# SUP_3_3_FMC.net
KiCad netlist of a schematic drawn in Altium Designer
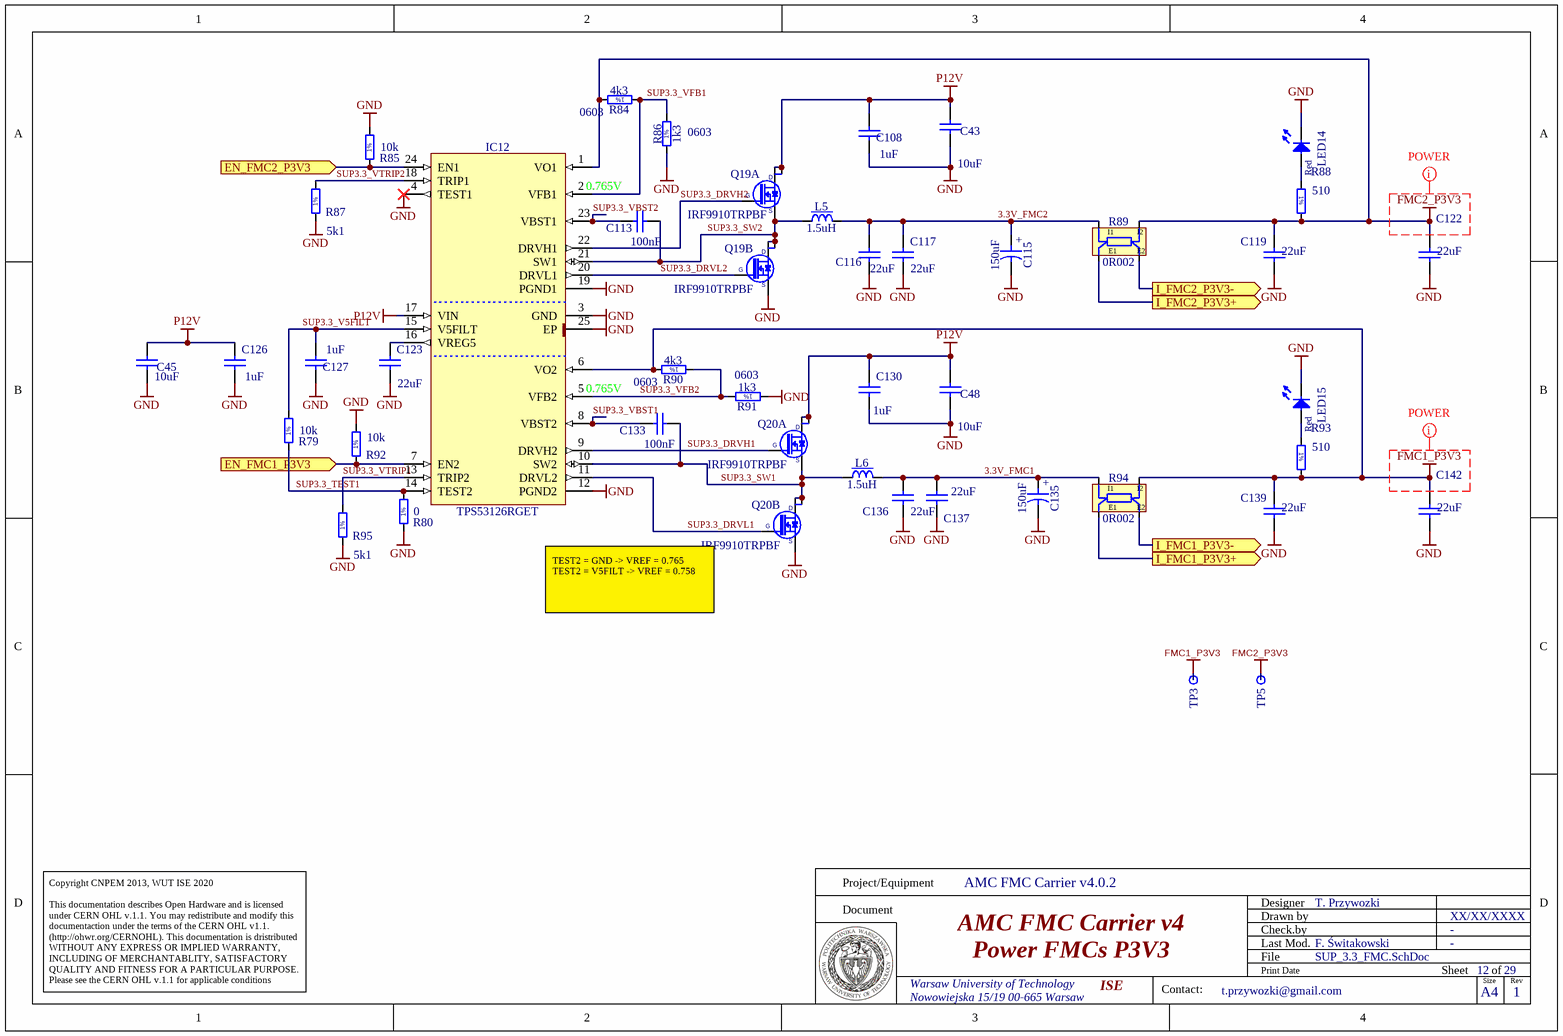
[diagram p0: SUP_3.3_FMC.SchDoc]

(export (version "E")
  (design (tool "Eeschema 10.0.6"))
  (components
    (comp (ref "C43")
      (value "10uF")
      (footprint "CAPC2012X135N")
      (description "Non-polarised capacitor")
      (fields
        (field (name "PART NUMBER") "CC0805_10UF_16V_10%_X5R")
        (field (name "VOLTAGE") "16V")
        (field (name "AUTHOR") "CERN DEM JLC")
      )
      (libsource (lib "Capacitors") (part "Capacitor - non polarized"))
    )
    (comp (ref "C45")
      (value "10uF")
      (footprint "CAPC2012X135N")
      (description "Non-polarised capacitor")
      (fields
        (field (name "PART NUMBER") "CC0805_10UF_16V_10%_X5R")
        (field (name "VOLTAGE") "16V")
        (field (name "AUTHOR") "CERN DEM JLC")
      )
      (libsource (lib "Capacitors") (part "Capacitor - non polarized"))
    )
    (comp (ref "C48")
      (value "10uF")
      (footprint "CAPC2012X135N")
      (description "Non-polarised capacitor")
      (fields
        (field (name "PART NUMBER") "CC0805_10UF_16V_10%_X5R")
        (field (name "VOLTAGE") "16V")
        (field (name "AUTHOR") "CERN DEM JLC")
      )
      (libsource (lib "Capacitors") (part "Capacitor - non polarized"))
    )
    (comp (ref "C108")
      (value "1uF")
      (footprint "CAPC1608X87N")
      (description "Non-polarised capacitor")
      (fields
        (field (name "PART NUMBER") "CC0603_1UF_16V_10%_X7R")
        (field (name "VOLTAGE") "16V")
        (field (name "AUTHOR") "CERN DEM JLC")
      )
      (libsource (lib "Capacitors") (part "Capacitor - non polarized"))
    )
    (comp (ref "C113")
      (value "100nF")
      (footprint "CAPC1005X55N")
      (description "Non-polarised capacitor")
      (fields
        (field (name "PART NUMBER") "CC0402_100NF_16V_10%_X7R")
        (field (name "VOLTAGE") "16V")
        (field (name "AUTHOR") "CERN DEM JLC")
      )
      (libsource (lib "Capacitors") (part "Capacitor - non polarized"))
    )
    (comp (ref "C115")
      (value "150uF")
      (footprint "CAPMP7343X200N")
      (description "Polarised capacitor")
      (fields
        (field (name "PART NUMBER") "CAEM7343-20_150UF_4V_20%_LESR0016")
        (field (name "VOLTAGE") "4V")
        (field (name "AUTHOR") "CERN DEM JLC")
      )
      (libsource (lib "Capacitors") (part "Capacitor - polarized"))
    )
    (comp (ref "C116")
      (value "22uF")
      (footprint "CAPC3216X180N")
      (description "Non-polarised capacitor")
      (fields
        (field (name "PART NUMBER") "CC1206_22UF_10V_10%_X7R")
        (field (name "VOLTAGE") "10V")
        (field (name "AUTHOR") "CERN DEM JLC")
      )
      (libsource (lib "Capacitors") (part "Capacitor - non polarized"))
    )
    (comp (ref "C117")
      (value "22uF")
      (footprint "CAPC3216X180N")
      (description "Non-polarised capacitor")
      (fields
        (field (name "PART NUMBER") "CC1206_22UF_10V_10%_X7R")
        (field (name "VOLTAGE") "10V")
        (field (name "AUTHOR") "CERN DEM JLC")
      )
      (libsource (lib "Capacitors") (part "Capacitor - non polarized"))
    )
    (comp (ref "C119")
      (value "22uF")
      (footprint "CAPC3216X180N")
      (description "Non-polarised capacitor")
      (fields
        (field (name "PART NUMBER") "CC1206_22UF_10V_10%_X7R")
        (field (name "VOLTAGE") "10V")
        (field (name "AUTHOR") "CERN DEM JLC")
      )
      (libsource (lib "Capacitors") (part "Capacitor - non polarized"))
    )
    (comp (ref "C122")
      (value "22uF")
      (footprint "CAPC3216X180N")
      (description "Non-polarised capacitor")
      (fields
        (field (name "PART NUMBER") "CC1206_22UF_10V_10%_X7R")
        (field (name "VOLTAGE") "10V")
        (field (name "AUTHOR") "CERN DEM JLC")
      )
      (libsource (lib "Capacitors") (part "Capacitor - non polarized"))
    )
    (comp (ref "C123")
      (value "22uF")
      (footprint "CAPC3216X180N")
      (description "Non-polarised capacitor")
      (fields
        (field (name "PART NUMBER") "CC1206_22UF_10V_10%_X7R")
        (field (name "VOLTAGE") "10V")
        (field (name "AUTHOR") "CERN DEM JLC")
      )
      (libsource (lib "Capacitors") (part "Capacitor - non polarized"))
    )
    (comp (ref "C126")
      (value "1uF")
      (footprint "CAPC1608X87N")
      (description "Non-polarised capacitor")
      (fields
        (field (name "PART NUMBER") "CC0603_1UF_16V_10%_X7R")
        (field (name "VOLTAGE") "16V")
        (field (name "AUTHOR") "CERN DEM JLC")
      )
      (libsource (lib "Capacitors") (part "Capacitor - non polarized"))
    )
    (comp (ref "C127")
      (value "1uF")
      (footprint "CAPC1608X87N")
      (description "Non-polarised capacitor")
      (fields
        (field (name "PART NUMBER") "CC0603_1UF_16V_10%_X7R")
        (field (name "VOLTAGE") "16V")
        (field (name "AUTHOR") "CERN DEM JLC")
      )
      (libsource (lib "Capacitors") (part "Capacitor - non polarized"))
    )
    (comp (ref "C130")
      (value "1uF")
      (footprint "CAPC1608X87N")
      (description "Non-polarised capacitor")
      (fields
        (field (name "PART NUMBER") "CC0603_1UF_16V_10%_X7R")
        (field (name "VOLTAGE") "16V")
        (field (name "AUTHOR") "CERN DEM JLC")
      )
      (libsource (lib "Capacitors") (part "Capacitor - non polarized"))
    )
    (comp (ref "C133")
      (value "100nF")
      (footprint "CAPC1005X55N")
      (description "Non-polarised capacitor")
      (fields
        (field (name "PART NUMBER") "CC0402_100NF_16V_10%_X7R")
        (field (name "VOLTAGE") "16V")
        (field (name "AUTHOR") "CERN DEM JLC")
      )
      (libsource (lib "Capacitors") (part "Capacitor - non polarized"))
    )
    (comp (ref "C135")
      (value "150uF")
      (footprint "CAPMP7343X200N")
      (description "Polarised capacitor")
      (fields
        (field (name "PART NUMBER") "CAEM7343-20_150UF_4V_20%_LESR0016")
        (field (name "VOLTAGE") "4V")
        (field (name "AUTHOR") "CERN DEM JLC")
      )
      (libsource (lib "Capacitors") (part "Capacitor - polarized"))
    )
    (comp (ref "C136")
      (value "22uF")
      (footprint "CAPC3216X180N")
      (description "Non-polarised capacitor")
      (fields
        (field (name "PART NUMBER") "CC1206_22UF_10V_10%_X7R")
        (field (name "VOLTAGE") "10V")
        (field (name "AUTHOR") "CERN DEM JLC")
      )
      (libsource (lib "Capacitors") (part "Capacitor - non polarized"))
    )
    (comp (ref "C137")
      (value "22uF")
      (footprint "CAPC3216X180N")
      (description "Non-polarised capacitor")
      (fields
        (field (name "PART NUMBER") "CC1206_22UF_10V_10%_X7R")
        (field (name "VOLTAGE") "10V")
        (field (name "AUTHOR") "CERN DEM JLC")
      )
      (libsource (lib "Capacitors") (part "Capacitor - non polarized"))
    )
    (comp (ref "C139")
      (value "22uF")
      (footprint "CAPC3216X180N")
      (description "Non-polarised capacitor")
      (fields
        (field (name "PART NUMBER") "CC1206_22UF_10V_10%_X7R")
        (field (name "VOLTAGE") "10V")
        (field (name "AUTHOR") "CERN DEM JLC")
      )
      (libsource (lib "Capacitors") (part "Capacitor - non polarized"))
    )
    (comp (ref "C142")
      (value "22uF")
      (footprint "CAPC3216X180N")
      (description "Non-polarised capacitor")
      (fields
        (field (name "PART NUMBER") "CC1206_22UF_10V_10%_X7R")
        (field (name "VOLTAGE") "10V")
        (field (name "AUTHOR") "CERN DEM JLC")
      )
      (libsource (lib "Capacitors") (part "Capacitor - non polarized"))
    )
    (comp (ref "IC12")
      (value "TPS53126RGET")
      (footprint "QFN50P400X400X100-25N-S255")
      (description "Dual Synchronous Step-Down Controller For Low Voltage Power Rails")
      (fields (field (name "MANUFACTURER") "TEXAS INSTRUMENTS") (field (name "AUTHOR") "CERN DEM JLC"))
      (libsource (lib "ICs And Semiconductors") (part "TPS53126RGET"))
    )
    (comp (ref "L5")
      (value "1.5uH")
      (footprint "IND_TDK_SPM6530")
      (description "Inductor With Core")
      (fields
        (field (name "PART NUMBER") "IND_1.5UH_20%_TDK_SPM6530")
        (field (name "POWER") "11A")
        (field (name "AUTHOR") "CERN DEM MR")
      )
      (libsource (lib "Inductors & Transformers") (part "Inductor With Magnetic core"))
    )
    (comp (ref "L6")
      (value "1.5uH")
      (footprint "IND_TDK_SPM6530")
      (description "Inductor With Core")
      (fields
        (field (name "PART NUMBER") "IND_1.5UH_20%_TDK_SPM6530")
        (field (name "POWER") "11A")
        (field (name "AUTHOR") "CERN DEM MR")
      )
      (libsource (lib "Inductors & Transformers") (part "Inductor With Magnetic core"))
    )
    (comp (ref "LED14")
      (value "Red")
      (footprint "LED_KINGBRIGHT_KPH-1608SURCK")
      (description "LED Red 1C 2A")
      (fields
        (field (name "PART NUMBER") "LED_KINGBRIGHT_KPH-1608SURCK")
        (field (name "MANUFACTURER") "KINGBRIGHT")
        (field (name "AUTHOR") "CERN DEM JLC")
      )
      (libsource (lib "ICs And Semiconductors") (part "LED Red 1C 2A"))
    )
    (comp (ref "LED15")
      (value "Red")
      (footprint "LED_KINGBRIGHT_KPH-1608SURCK")
      (description "LED Red 1C 2A")
      (fields
        (field (name "PART NUMBER") "LED_KINGBRIGHT_KPH-1608SURCK")
        (field (name "MANUFACTURER") "KINGBRIGHT")
        (field (name "AUTHOR") "CERN DEM JLC")
      )
      (libsource (lib "ICs And Semiconductors") (part "LED Red 1C 2A"))
    )
    (comp (ref "Q19")
      (value "IRF9910TRPBF")
      (footprint "SOIC127P600X175-8N")
      (description "Dual SO-8 MOSFET For POL Cconverter")
      (fields (field (name "MANUFACTURER") "INTERNATIONAL RECTIFIER") (field (name "AUTHOR") "TP"))
      (libsource (lib "AMC_FMC_Carrier") (part "IRF9910"))
    )
    (comp (ref "Q20")
      (value "IRF9910TRPBF")
      (footprint "SOIC127P600X175-8N")
      (description "Dual SO-8 MOSFET For POL Cconverter")
      (fields (field (name "MANUFACTURER") "INTERNATIONAL RECTIFIER") (field (name "AUTHOR") "TP"))
      (libsource (lib "AMC_FMC_Carrier") (part "IRF9910"))
    )
    (comp (ref "R79")
      (value "10k")
      (footprint "RESC1005X40N")
      (description "Resistor - 1%")
      (fields
        (field (name "PART NUMBER") "R0402_10K_1%_0.0625W_100PPM")
        (field (name "POWER") "0.0625W")
        (field (name "AUTHOR") "CERN DEM JLC")
      )
      (libsource (lib "Resistors") (part "Resistor - 1%"))
    )
    (comp (ref "R80")
      (value "0")
      (footprint "RESC1005X40N")
      (description "Resistor - 1%")
      (fields
        (field (name "PART NUMBER") "R0402_0R_JUMPER")
        (field (name "MANUFACTURER") "GENERIC")
        (field (name "AUTHOR") "CERN DEM JLC")
      )
      (libsource (lib "Resistors") (part "Resistor - 1%"))
    )
    (comp (ref "R84")
      (value "4k3")
      (footprint "RESC1608X55N")
      (description "Resistor - 1%")
      (fields
        (field (name "PART NUMBER") "R0603_4K3_1%_0.1W_100PPM")
        (field (name "POWER") "0.1W")
        (field (name "CASE") "0603")
        (field (name "AUTHOR") "CERN DEM JLC")
      )
      (libsource (lib "Resistors") (part "Resistor - 1%"))
    )
    (comp (ref "R85")
      (value "10k")
      (footprint "RESC1005X40N")
      (description "Resistor - 1%")
      (fields
        (field (name "PART NUMBER") "R0402_10K_1%_0.0625W_100PPM")
        (field (name "POWER") "0.0625W")
        (field (name "AUTHOR") "CERN DEM JLC")
      )
      (libsource (lib "Resistors") (part "Resistor - 1%"))
    )
    (comp (ref "R86")
      (value "1k3")
      (footprint "RESC1608X55N")
      (description "Resistor - 1%")
      (fields
        (field (name "PART NUMBER") "R0603_1K3_1%_0.1W_100PPM")
        (field (name "POWER") "0.1W")
        (field (name "CASE") "0603")
        (field (name "AUTHOR") "CERN DEM JLC")
      )
      (libsource (lib "Resistors") (part "Resistor - 1%"))
    )
    (comp (ref "R87")
      (value "5k1")
      (footprint "RESC1608X55N")
      (description "Resistor - 1%")
      (fields
        (field (name "PART NUMBER") "R0603_5K1_1%_0.1W_100PPM")
        (field (name "POWER") "0.1W")
        (field (name "AUTHOR") "CERN DEM JLC")
      )
      (libsource (lib "Resistors") (part "Resistor - 1%"))
    )
    (comp (ref "R88")
      (value "510")
      (footprint "RESC1005X40N")
      (description "Resistor - 1%")
      (fields
        (field (name "PART NUMBER") "R0402_510R_1%_0.0625W_100PPM")
        (field (name "POWER") "0.0625W")
        (field (name "AUTHOR") "CERN DEM JLC")
      )
      (libsource (lib "Resistors") (part "Resistor - 1%"))
    )
    (comp (ref "R89")
      (value "0R002")
      (footprint "RES_VISHAY_WSK2512_0R005-0R2")
      (description "Power and Current Sensing Resistor")
      (fields
        (field (name "PART NUMBER") "R2512_0R002_1%_1W_35PPM_VISHAY_WSK")
        (field (name "POWER") "1W")
        (field (name "AUTHOR") "CERN DEM MR")
      )
      (libsource (lib "Resistors") (part "Current Sense Resistor"))
    )
    (comp (ref "R90")
      (value "4k3")
      (footprint "RESC1608X55N")
      (description "Resistor - 1%")
      (fields
        (field (name "PART NUMBER") "R0603_4K3_1%_0.1W_100PPM")
        (field (name "POWER") "0.1W")
        (field (name "CASE") "0603")
        (field (name "AUTHOR") "CERN DEM JLC")
      )
      (libsource (lib "Resistors") (part "Resistor - 1%"))
    )
    (comp (ref "R91")
      (value "1k3")
      (footprint "RESC1608X55N")
      (description "Resistor - 1%")
      (fields
        (field (name "PART NUMBER") "R0603_1K3_1%_0.1W_100PPM")
        (field (name "POWER") "0.1W")
        (field (name "CASE") "0603")
        (field (name "AUTHOR") "CERN DEM JLC")
      )
      (libsource (lib "Resistors") (part "Resistor - 1%"))
    )
    (comp (ref "R92")
      (value "10k")
      (footprint "RESC1005X40N")
      (description "Resistor - 1%")
      (fields
        (field (name "PART NUMBER") "R0402_10K_1%_0.0625W_100PPM")
        (field (name "POWER") "0.0625W")
        (field (name "AUTHOR") "CERN DEM JLC")
      )
      (libsource (lib "Resistors") (part "Resistor - 1%"))
    )
    (comp (ref "R93")
      (value "510")
      (footprint "RESC1005X40N")
      (description "Resistor - 1%")
      (fields
        (field (name "PART NUMBER") "R0402_510R_1%_0.0625W_100PPM")
        (field (name "POWER") "0.0625W")
        (field (name "AUTHOR") "CERN DEM JLC")
      )
      (libsource (lib "Resistors") (part "Resistor - 1%"))
    )
    (comp (ref "R94")
      (value "0R002")
      (footprint "RES_VISHAY_WSK2512_0R005-0R2")
      (description "Power and Current Sensing Resistor")
      (fields
        (field (name "PART NUMBER") "R2512_0R002_1%_1W_35PPM_VISHAY_WSK")
        (field (name "POWER") "1W")
        (field (name "AUTHOR") "CERN DEM MR")
      )
      (libsource (lib "Resistors") (part "Current Sense Resistor"))
    )
    (comp (ref "R95")
      (value "5k1")
      (footprint "RESC1608X55N")
      (description "Resistor - 1%")
      (fields
        (field (name "PART NUMBER") "R0603_5K1_1%_0.1W_100PPM")
        (field (name "POWER") "0.1W")
        (field (name "AUTHOR") "CERN DEM JLC")
      )
      (libsource (lib "Resistors") (part "Resistor - 1%"))
    )
    (comp (ref "TP3")
      (value "Test Point")
      (footprint "TPS127")
      (fields (field (name "PART NUMBER") "SMD_PAD_1.27X1.27MM") (field (name "AUTHOR") "CERN DEM JLC"))
      (libsource (lib "Eletro-mechanical") (part "Test Point"))
    )
    (comp (ref "TP5")
      (value "Test Point")
      (footprint "TPS127")
      (fields (field (name "PART NUMBER") "SMD_PAD_1.27X1.27MM") (field (name "AUTHOR") "CERN DEM JLC"))
      (libsource (lib "Eletro-mechanical") (part "Test Point"))
    )
  )
  (nets
    (net (code "1") (name "/3.3V_FMC1") (class "Default")
      (node (ref "C135") (pin "1") (pinfunction "1_1") (pintype "passive"))
      (node (ref "C136") (pin "1") (pinfunction "1_1") (pintype "passive"))
      (node (ref "C137") (pin "1") (pinfunction "1_1") (pintype "passive"))
      (node (ref "L6") (pin "2") (pinfunction "2_2") (pintype "passive"))
      (node (ref "R94") (pin "I1") (pinfunction "I1_I1") (pintype "passive"))
    )
    (net (code "2") (name "/3.3V_FMC2") (class "Default")
      (node (ref "C115") (pin "1") (pinfunction "1_1") (pintype "passive"))
      (node (ref "C116") (pin "1") (pinfunction "1_1") (pintype "passive"))
      (node (ref "C117") (pin "1") (pinfunction "1_1") (pintype "passive"))
      (node (ref "L5") (pin "2") (pinfunction "2_2") (pintype "passive"))
      (node (ref "R89") (pin "I1") (pinfunction "I1_I1") (pintype "passive"))
    )
    (net (code "3") (name "/EN_FMC1_P3V3") (class "Default")
      (node (ref "IC12") (pin "7") (pinfunction "EN2_7") (pintype "input"))
      (node (ref "R92") (pin "1") (pinfunction "1_1") (pintype "passive"))
    )
    (net (code "4") (name "/EN_FMC2_P3V3") (class "Default")
      (node (ref "IC12") (pin "24") (pinfunction "EN1_24") (pintype "input"))
      (node (ref "R85") (pin "1") (pinfunction "1_1") (pintype "passive"))
    )
    (net (code "5") (name "/I_FMC1_P3V3+") (class "Default")
      (node (ref "R94") (pin "E1") (pinfunction "E1_E1") (pintype "passive"))
    )
    (net (code "6") (name "/I_FMC1_P3V3-") (class "Default")
      (node (ref "R94") (pin "E2") (pinfunction "E2_E2") (pintype "passive"))
    )
    (net (code "7") (name "/I_FMC2_P3V3+") (class "Default")
      (node (ref "R89") (pin "E1") (pinfunction "E1_E1") (pintype "passive"))
    )
    (net (code "8") (name "/I_FMC2_P3V3-") (class "Default")
      (node (ref "R89") (pin "E2") (pinfunction "E2_E2") (pintype "passive"))
    )
    (net (code "9") (name "/SUP3.3_DRVH1") (class "Default")
      (node (ref "IC12") (pin "9") (pinfunction "DRVH2_9") (pintype "output"))
      (node (ref "Q20") (pin "4") (pinfunction "G_4") (pintype "passive"))
    )
    (net (code "10") (name "/SUP3.3_DRVH2") (class "Default")
      (node (ref "IC12") (pin "22") (pinfunction "DRVH1_22") (pintype "output"))
      (node (ref "Q19") (pin "4") (pinfunction "G_4") (pintype "passive"))
    )
    (net (code "11") (name "/SUP3.3_DRVL1") (class "Default")
      (node (ref "IC12") (pin "11") (pinfunction "DRVL2_11") (pintype "output"))
      (node (ref "Q20") (pin "2") (pinfunction "G_2") (pintype "passive"))
    )
    (net (code "12") (name "/SUP3.3_DRVL2") (class "Default")
      (node (ref "IC12") (pin "20") (pinfunction "DRVL1_20") (pintype "output"))
      (node (ref "Q19") (pin "2") (pinfunction "G_2") (pintype "passive"))
    )
    (net (code "13") (name "/SUP3.3_SW1") (class "Default")
      (node (ref "C133") (pin "1") (pinfunction "1_1") (pintype "passive"))
      (node (ref "IC12") (pin "10") (pinfunction "SW2_10") (pintype "bidirectional"))
      (node (ref "L6") (pin "1") (pinfunction "1_1") (pintype "passive"))
      (node (ref "Q20") (pin "3") (pinfunction "S_3") (pintype "passive"))
      (node (ref "Q20") (pin "7") (pinfunction "D_7") (pintype "passive"))
      (node (ref "Q20") (pin "8") (pinfunction "D_8") (pintype "passive"))
    )
    (net (code "14") (name "/SUP3.3_SW2") (class "Default")
      (node (ref "C113") (pin "1") (pinfunction "1_1") (pintype "passive"))
      (node (ref "IC12") (pin "21") (pinfunction "SW1_21") (pintype "bidirectional"))
      (node (ref "L5") (pin "1") (pinfunction "1_1") (pintype "passive"))
      (node (ref "Q19") (pin "3") (pinfunction "S_3") (pintype "passive"))
      (node (ref "Q19") (pin "7") (pinfunction "D_7") (pintype "passive"))
      (node (ref "Q19") (pin "8") (pinfunction "D_8") (pintype "passive"))
    )
    (net (code "15") (name "/SUP3.3_TEST1") (class "Default")
      (node (ref "IC12") (pin "14") (pinfunction "TEST2_14") (pintype "input"))
      (node (ref "R79") (pin "1") (pinfunction "1_1") (pintype "passive"))
      (node (ref "R80") (pin "2") (pinfunction "2_2") (pintype "passive"))
    )
    (net (code "16") (name "/SUP3.3_V5FILT") (class "Default")
      (node (ref "C127") (pin "2") (pinfunction "2_2") (pintype "passive"))
      (node (ref "IC12") (pin "15") (pinfunction "V5FILT_15") (pintype "input"))
      (node (ref "R79") (pin "2") (pinfunction "2_2") (pintype "passive"))
    )
    (net (code "17") (name "/SUP3.3_VBST1") (class "Default")
      (node (ref "C133") (pin "2") (pinfunction "2_2") (pintype "passive"))
      (node (ref "IC12") (pin "8") (pinfunction "VBST2_8") (pintype "input"))
    )
    (net (code "18") (name "/SUP3.3_VBST2") (class "Default")
      (node (ref "C113") (pin "2") (pinfunction "2_2") (pintype "passive"))
      (node (ref "IC12") (pin "23") (pinfunction "VBST1_23") (pintype "input"))
    )
    (net (code "19") (name "/SUP3.3_VFB1") (class "Default")
      (node (ref "IC12") (pin "2") (pinfunction "VFB1_2") (pintype "input"))
      (node (ref "R84") (pin "1") (pinfunction "1_1") (pintype "passive"))
      (node (ref "R86") (pin "2") (pinfunction "2_2") (pintype "passive"))
    )
    (net (code "20") (name "/SUP3.3_VFB2") (class "Default")
      (node (ref "IC12") (pin "5") (pinfunction "VFB2_5") (pintype "input"))
      (node (ref "R90") (pin "1") (pinfunction "1_1") (pintype "passive"))
      (node (ref "R91") (pin "2") (pinfunction "2_2") (pintype "passive"))
    )
    (net (code "21") (name "/SUP3.3_VTRIP1") (class "Default")
      (node (ref "IC12") (pin "13") (pinfunction "TRIP2_13") (pintype "input"))
      (node (ref "R95") (pin "2") (pinfunction "2_2") (pintype "passive"))
    )
    (net (code "22") (name "/SUP3.3_VTRIP2") (class "Default")
      (node (ref "IC12") (pin "18") (pinfunction "TRIP1_18") (pintype "input"))
      (node (ref "R87") (pin "2") (pinfunction "2_2") (pintype "passive"))
    )
    (net (code "23") (name "FMC1_P3V3") (class "Default")
      (node (ref "C139") (pin "1") (pinfunction "1_1") (pintype "passive"))
      (node (ref "C142") (pin "1") (pinfunction "1_1") (pintype "passive"))
      (node (ref "IC12") (pin "6") (pinfunction "VO2_6") (pintype "input"))
      (node (ref "R90") (pin "2") (pinfunction "2_2") (pintype "passive"))
      (node (ref "R93") (pin "2") (pinfunction "2_2") (pintype "passive"))
      (node (ref "R94") (pin "I2") (pinfunction "I2_I2") (pintype "passive"))
      (node (ref "TP3") (pin "1") (pinfunction "1_1") (pintype "bidirectional"))
    )
    (net (code "24") (name "FMC2_P3V3") (class "Default")
      (node (ref "C119") (pin "1") (pinfunction "1_1") (pintype "passive"))
      (node (ref "C122") (pin "1") (pinfunction "1_1") (pintype "passive"))
      (node (ref "IC12") (pin "1") (pinfunction "VO1_1") (pintype "input"))
      (node (ref "R84") (pin "2") (pinfunction "2_2") (pintype "passive"))
      (node (ref "R88") (pin "2") (pinfunction "2_2") (pintype "passive"))
      (node (ref "R89") (pin "I2") (pinfunction "I2_I2") (pintype "passive"))
      (node (ref "TP5") (pin "1") (pinfunction "1_1") (pintype "bidirectional"))
    )
    (net (code "25") (name "GND") (class "Default")
      (node (ref "C108") (pin "1") (pinfunction "1_1") (pintype "passive"))
      (node (ref "C115") (pin "2") (pinfunction "2_2") (pintype "passive"))
      (node (ref "C116") (pin "2") (pinfunction "2_2") (pintype "passive"))
      (node (ref "C117") (pin "2") (pinfunction "2_2") (pintype "passive"))
      (node (ref "C119") (pin "2") (pinfunction "2_2") (pintype "passive"))
      (node (ref "C122") (pin "2") (pinfunction "2_2") (pintype "passive"))
      (node (ref "C123") (pin "1") (pinfunction "1_1") (pintype "passive"))
      (node (ref "C126") (pin "1") (pinfunction "1_1") (pintype "passive"))
      (node (ref "C127") (pin "1") (pinfunction "1_1") (pintype "passive"))
      (node (ref "C130") (pin "1") (pinfunction "1_1") (pintype "passive"))
      (node (ref "C135") (pin "2") (pinfunction "2_2") (pintype "passive"))
      (node (ref "C136") (pin "2") (pinfunction "2_2") (pintype "passive"))
      (node (ref "C137") (pin "2") (pinfunction "2_2") (pintype "passive"))
      (node (ref "C139") (pin "2") (pinfunction "2_2") (pintype "passive"))
      (node (ref "C142") (pin "2") (pinfunction "2_2") (pintype "passive"))
      (node (ref "C43") (pin "1") (pinfunction "1_1") (pintype "passive"))
      (node (ref "C45") (pin "1") (pinfunction "1_1") (pintype "passive"))
      (node (ref "C48") (pin "1") (pinfunction "1_1") (pintype "passive"))
      (node (ref "IC12") (pin "12") (pinfunction "PGND2_12") (pintype "power_in"))
      (node (ref "IC12") (pin "19") (pinfunction "PGND1_19") (pintype "power_in"))
      (node (ref "IC12") (pin "25") (pinfunction "EP_25") (pintype "power_in"))
      (node (ref "IC12") (pin "3") (pinfunction "GND_3") (pintype "power_in"))
      (node (ref "IC12") (pin "4") (pinfunction "TEST1_4") (pintype "output"))
      (node (ref "LED14") (pin "1") (pinfunction "C_1") (pintype "passive"))
      (node (ref "LED15") (pin "1") (pinfunction "C_1") (pintype "passive"))
      (node (ref "Q19") (pin "1") (pinfunction "S_1") (pintype "passive"))
      (node (ref "Q20") (pin "1") (pinfunction "S_1") (pintype "passive"))
      (node (ref "R80") (pin "1") (pinfunction "1_1") (pintype "passive"))
      (node (ref "R85") (pin "2") (pinfunction "2_2") (pintype "passive"))
      (node (ref "R86") (pin "1") (pinfunction "1_1") (pintype "passive"))
      (node (ref "R87") (pin "1") (pinfunction "1_1") (pintype "passive"))
      (node (ref "R91") (pin "1") (pinfunction "1_1") (pintype "passive"))
      (node (ref "R92") (pin "2") (pinfunction "2_2") (pintype "passive"))
      (node (ref "R95") (pin "1") (pinfunction "1_1") (pintype "passive"))
    )
    (net (code "26") (name "Net-(IC12-VREG5)") (class "Default")
      (node (ref "C123") (pin "2") (pinfunction "2_2") (pintype "passive"))
      (node (ref "IC12") (pin "16") (pinfunction "VREG5_16") (pintype "output"))
    )
    (net (code "27") (name "Net-(LED14-A)") (class "Default")
      (node (ref "LED14") (pin "2") (pinfunction "A_2") (pintype "passive"))
      (node (ref "R88") (pin "1") (pinfunction "1_1") (pintype "passive"))
    )
    (net (code "28") (name "Net-(LED15-A)") (class "Default")
      (node (ref "LED15") (pin "2") (pinfunction "A_2") (pintype "passive"))
      (node (ref "R93") (pin "1") (pinfunction "1_1") (pintype "passive"))
    )
    (net (code "29") (name "P12V") (class "Default")
      (node (ref "C108") (pin "2") (pinfunction "2_2") (pintype "passive"))
      (node (ref "C126") (pin "2") (pinfunction "2_2") (pintype "passive"))
      (node (ref "C130") (pin "2") (pinfunction "2_2") (pintype "passive"))
      (node (ref "C43") (pin "2") (pinfunction "2_2") (pintype "passive"))
      (node (ref "C45") (pin "2") (pinfunction "2_2") (pintype "passive"))
      (node (ref "C48") (pin "2") (pinfunction "2_2") (pintype "passive"))
      (node (ref "IC12") (pin "17") (pinfunction "VIN_17") (pintype "input"))
      (node (ref "Q19") (pin "5") (pinfunction "D_5") (pintype "passive"))
      (node (ref "Q19") (pin "6") (pinfunction "D_6") (pintype "passive"))
      (node (ref "Q20") (pin "5") (pinfunction "D_5") (pintype "passive"))
      (node (ref "Q20") (pin "6") (pinfunction "D_6") (pintype "passive"))
    )
  )
)
